# peggy-optical-board.net
KiCad netlist of a schematic drawn in Altium Designer
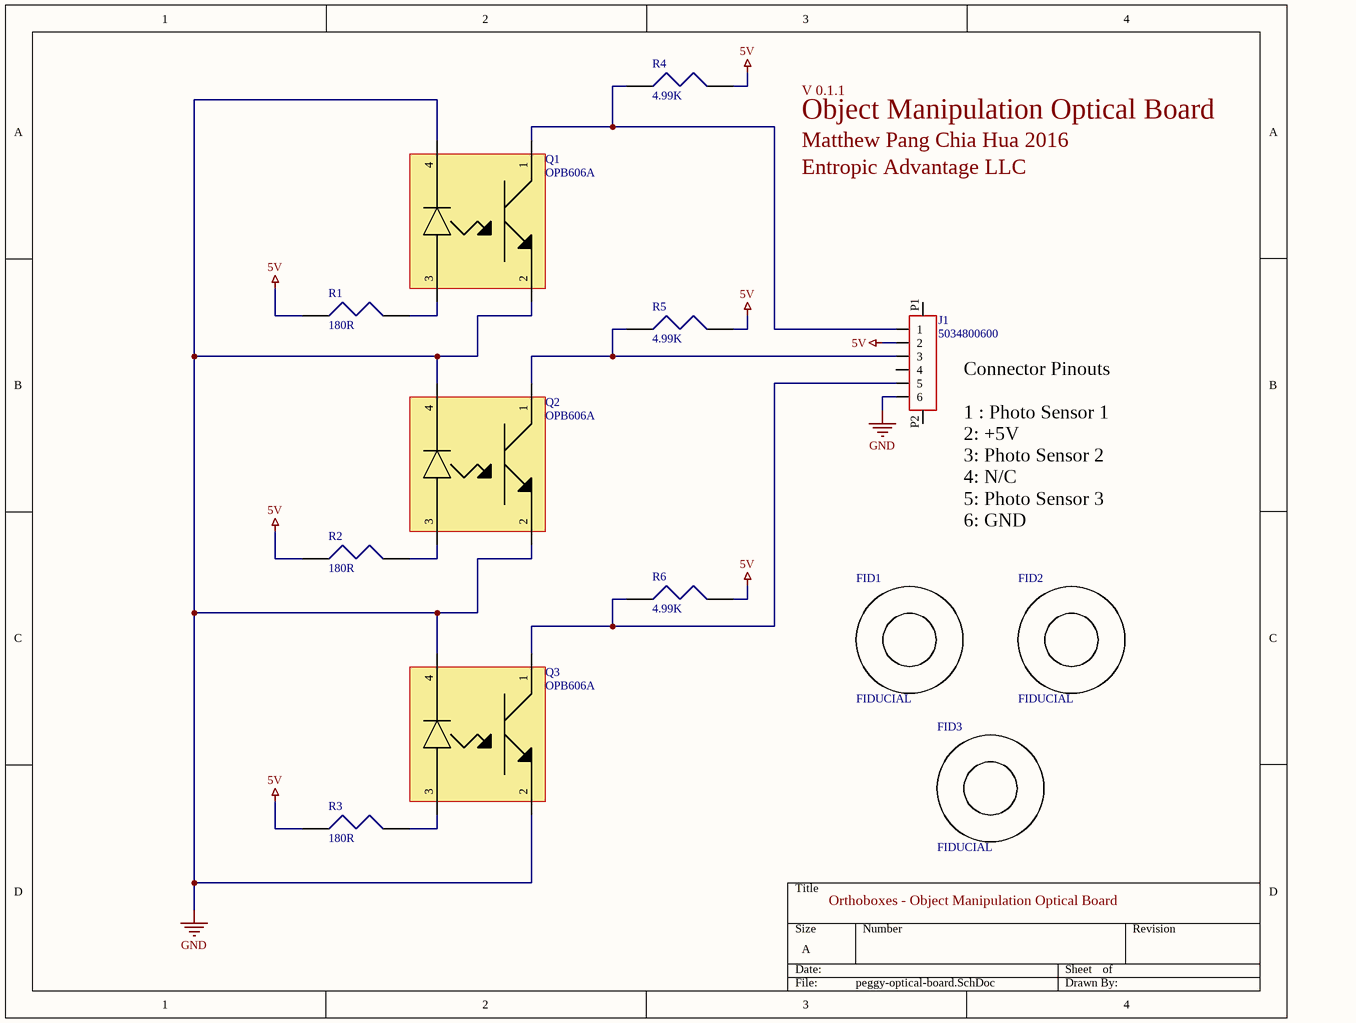
[diagram p0: peggy-optical-board.SchDoc]

(export (version "E")
  (design (tool "Eeschema 10.0.6"))
  (components
    (comp (ref "FID1")
      (value "FIDUCIAL")
      (footprint "FID")
      (libsource (lib "peggy-optical-board") (part "Fiducial 1"))
    )
    (comp (ref "FID2")
      (value "FIDUCIAL")
      (footprint "FID")
      (libsource (lib "peggy-optical-board") (part "Fiducial 1"))
    )
    (comp (ref "FID3")
      (value "FIDUCIAL")
      (footprint "FID")
      (libsource (lib "peggy-optical-board") (part "Fiducial 1"))
    )
    (comp (ref "J1")
      (value "5034800600")
      (footprint "MOLEX 503480-0600")
      (description "CONN FFC FPC 6POS 0.50MM R/A")
      (fields (field (name "MANUFACTURER") "Molex, LLC"))
      (libsource (lib "generic 32u4") (part "5034800600"))
    )
    (comp (ref "Q1")
      (value "OPB606A")
      (footprint "OPB606A")
      (description "SENSR OPTO TRANS 1.27MM REFL PCB")
      (fields (field (name "MANUFACTURER") "TT Electronics/Optek Technology"))
      (libsource (lib "generic 32u4") (part "OPB606A"))
    )
    (comp (ref "Q2")
      (value "OPB606A")
      (footprint "OPB606A")
      (description "SENSR OPTO TRANS 1.27MM REFL PCB")
      (fields (field (name "MANUFACTURER") "TT Electronics/Optek Technology"))
      (libsource (lib "generic 32u4") (part "OPB606A"))
    )
    (comp (ref "Q3")
      (value "OPB606A")
      (footprint "OPB606A")
      (description "SENSR OPTO TRANS 1.27MM REFL PCB")
      (fields (field (name "MANUFACTURER") "TT Electronics/Optek Technology"))
      (libsource (lib "generic 32u4") (part "OPB606A"))
    )
    (comp (ref "R1")
      (value "180R")
      (footprint "RESC2012X07N_SAMSUNG")
      (description "RES SMD 180 OHM 1% 1/8W 0805")
      (fields
        (field (name "MANUFACTURER") "Samsung Electro-Mechanics America, Inc.")
        (field (name "MANUFACTURER PART NUMBER") "RC2012F181CS")
      )
      (libsource (lib "generic 32u4") (part "RC2012F181CS"))
    )
    (comp (ref "R2")
      (value "180R")
      (footprint "RESC2012X07N_SAMSUNG")
      (description "RES SMD 180 OHM 1% 1/8W 0805")
      (fields
        (field (name "MANUFACTURER") "Samsung Electro-Mechanics America, Inc.")
        (field (name "MANUFACTURER PART NUMBER") "RC2012F181CS")
      )
      (libsource (lib "generic 32u4") (part "RC2012F181CS"))
    )
    (comp (ref "R3")
      (value "180R")
      (footprint "RESC2012X07N_SAMSUNG")
      (description "RES SMD 180 OHM 1% 1/8W 0805")
      (fields
        (field (name "MANUFACTURER") "Samsung Electro-Mechanics America, Inc.")
        (field (name "MANUFACTURER PART NUMBER") "RC2012F181CS")
      )
      (libsource (lib "generic 32u4") (part "RC2012F181CS"))
    )
    (comp (ref "R4")
      (value "4.99K")
      (footprint "RESC2012X07N_SAMSUNG")
      (description "RES SMD 4.99K OHM 1% 1/8W 0805")
      (fields
        (field (name "MANUFACTURER") "Samsung Electro-Mechanics America, Inc.")
        (field (name "MANUFACTURER PART NUMBER") "RC2012F4991CS")
      )
      (libsource (lib "generic 32u4") (part "RC2012F4991CS"))
    )
    (comp (ref "R5")
      (value "4.99K")
      (footprint "RESC2012X07N_SAMSUNG")
      (description "RES SMD 4.99K OHM 1% 1/8W 0805")
      (fields
        (field (name "MANUFACTURER") "Samsung Electro-Mechanics America, Inc.")
        (field (name "MANUFACTURER PART NUMBER") "RC2012F4991CS")
      )
      (libsource (lib "generic 32u4") (part "RC2012F4991CS"))
    )
    (comp (ref "R6")
      (value "4.99K")
      (footprint "RESC2012X07N_SAMSUNG")
      (description "RES SMD 4.99K OHM 1% 1/8W 0805")
      (fields
        (field (name "MANUFACTURER") "Samsung Electro-Mechanics America, Inc.")
        (field (name "MANUFACTURER PART NUMBER") "RC2012F4991CS")
      )
      (libsource (lib "generic 32u4") (part "RC2012F4991CS"))
    )
  )
  (nets
    (net (code "1") (name "5V") (class "Default")
      (node (ref "J1") (pin "2") (pinfunction "2_2") (pintype "passive"))
      (node (ref "R1") (pin "1") (pinfunction "1_1") (pintype "passive"))
      (node (ref "R2") (pin "1") (pinfunction "1_1") (pintype "passive"))
      (node (ref "R3") (pin "1") (pinfunction "1_1") (pintype "passive"))
      (node (ref "R4") (pin "2") (pinfunction "2_2") (pintype "passive"))
      (node (ref "R5") (pin "2") (pinfunction "2_2") (pintype "passive"))
      (node (ref "R6") (pin "2") (pinfunction "2_2") (pintype "passive"))
    )
    (net (code "2") (name "GND") (class "Default")
      (node (ref "J1") (pin "6") (pinfunction "6_6") (pintype "passive"))
      (node (ref "Q1") (pin "2") (pinfunction "2_2") (pintype "passive"))
      (node (ref "Q1") (pin "4") (pinfunction "4_4") (pintype "passive"))
      (node (ref "Q2") (pin "2") (pinfunction "2_2") (pintype "passive"))
      (node (ref "Q2") (pin "4") (pinfunction "4_4") (pintype "passive"))
      (node (ref "Q3") (pin "2") (pinfunction "2_2") (pintype "passive"))
      (node (ref "Q3") (pin "4") (pinfunction "4_4") (pintype "passive"))
    )
    (net (code "3") (name "Net-(J1-Pad1)") (class "Default")
      (node (ref "J1") (pin "1") (pinfunction "1_1") (pintype "passive"))
      (node (ref "Q1") (pin "1") (pinfunction "1_1") (pintype "passive"))
      (node (ref "R4") (pin "1") (pinfunction "1_1") (pintype "passive"))
    )
    (net (code "4") (name "Net-(J1-Pad3)") (class "Default")
      (node (ref "J1") (pin "3") (pinfunction "3_3") (pintype "passive"))
      (node (ref "Q2") (pin "1") (pinfunction "1_1") (pintype "passive"))
      (node (ref "R5") (pin "1") (pinfunction "1_1") (pintype "passive"))
    )
    (net (code "5") (name "Net-(J1-Pad5)") (class "Default")
      (node (ref "J1") (pin "5") (pinfunction "5_5") (pintype "passive"))
      (node (ref "Q3") (pin "1") (pinfunction "1_1") (pintype "passive"))
      (node (ref "R6") (pin "1") (pinfunction "1_1") (pintype "passive"))
    )
    (net (code "6") (name "Net-(Q1-Pad3)") (class "Default")
      (node (ref "Q1") (pin "3") (pinfunction "3_3") (pintype "passive"))
      (node (ref "R1") (pin "2") (pinfunction "2_2") (pintype "passive"))
    )
    (net (code "7") (name "Net-(Q2-Pad3)") (class "Default")
      (node (ref "Q2") (pin "3") (pinfunction "3_3") (pintype "passive"))
      (node (ref "R2") (pin "2") (pinfunction "2_2") (pintype "passive"))
    )
    (net (code "8") (name "Net-(Q3-Pad3)") (class "Default")
      (node (ref "Q3") (pin "3") (pinfunction "3_3") (pintype "passive"))
      (node (ref "R3") (pin "2") (pinfunction "2_2") (pintype "passive"))
    )
    (net (code "9") (name "unconnected-(J1-Pad4)") (class "Default")
      (node (ref "J1") (pin "4") (pinfunction "4_4") (pintype "passive"))
    )
    (net (code "10") (name "unconnected-(J1-PadP1)") (class "Default")
      (node (ref "J1") (pin "P1") (pinfunction "P1_P1") (pintype "passive"))
    )
    (net (code "11") (name "unconnected-(J1-PadP2)") (class "Default")
      (node (ref "J1") (pin "P2") (pinfunction "P2_P2") (pintype "passive"))
    )
  )
)
